# Naninator_and_Badger.net
KiCad netlist of a schematic drawn in EAGLE
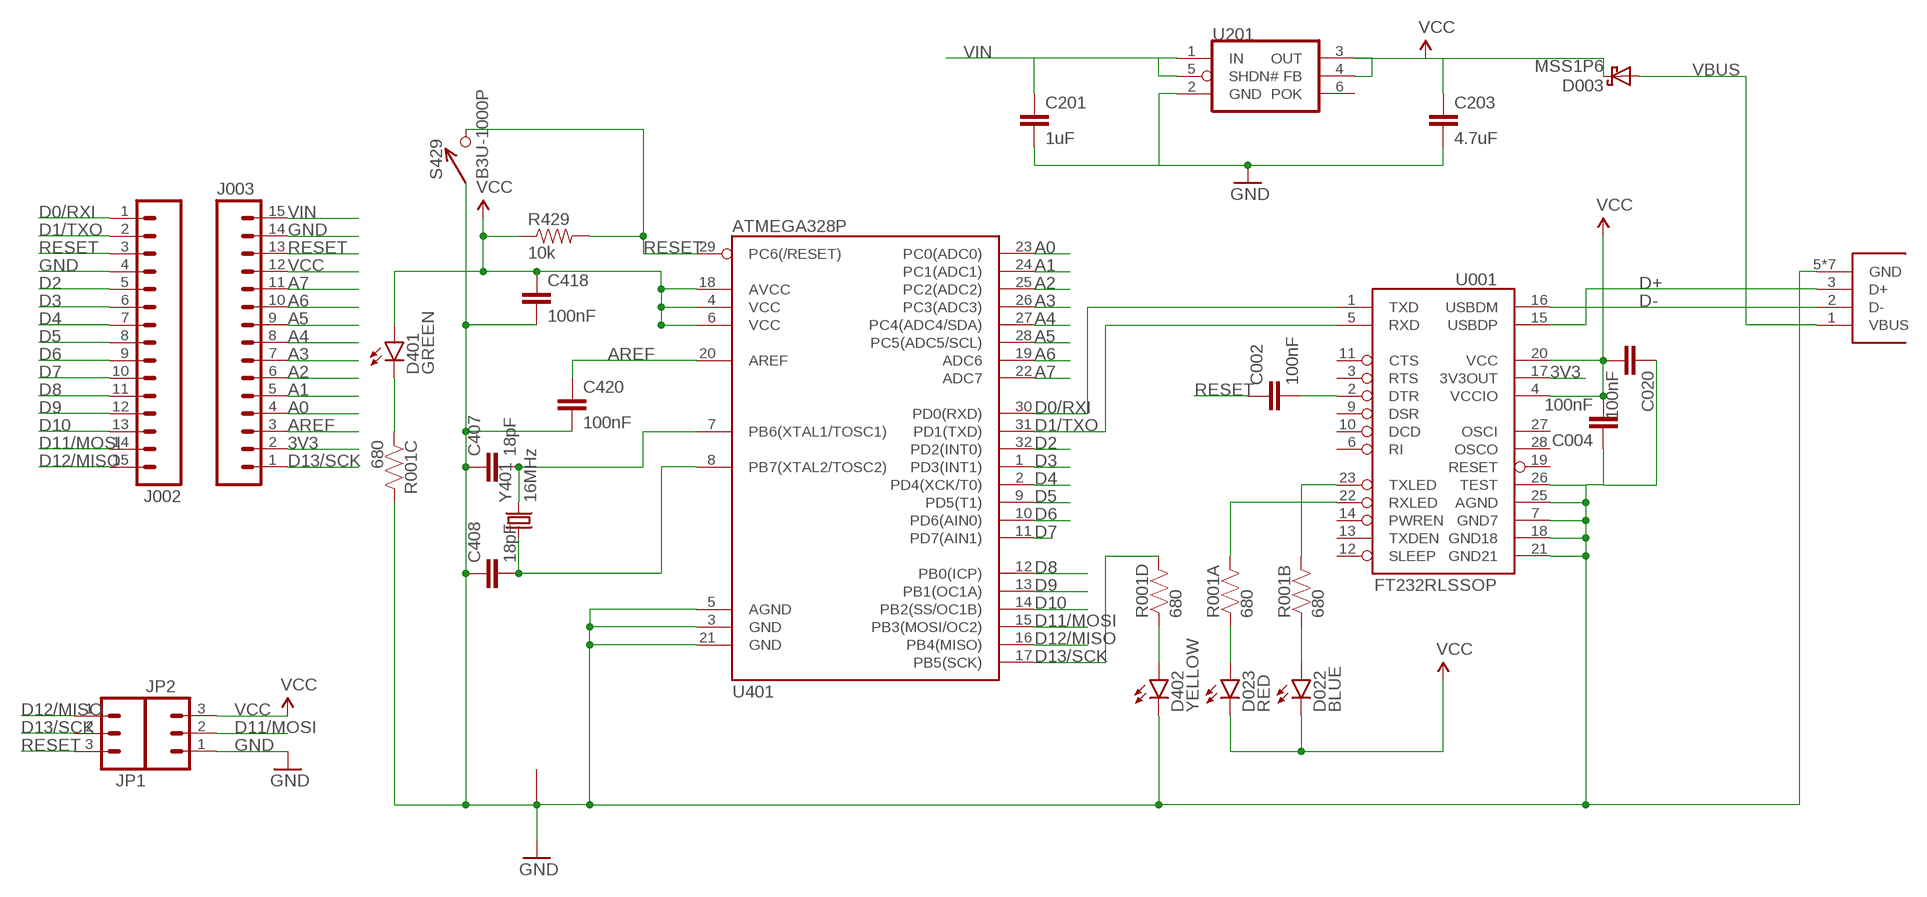
[diagram p0: schematic, sheet 1]

(export (version "E")
  (design (tool "Eeschema 10.0.6"))
  (components
    (comp (ref "C002")
      (value "100nF")
      (footprint "eagle-import:0402-CAP")
      (libsource (lib "eagle-import") (part "CAP0402-CAP"))
    )
    (comp (ref "C004")
      (value "100nF")
      (footprint "eagle-import:0402-CAP")
      (libsource (lib "eagle-import") (part "CAP0402-CAP"))
    )
    (comp (ref "C020")
      (value "100nF")
      (footprint "eagle-import:0402-CAP")
      (libsource (lib "eagle-import") (part "CAP0402-CAP"))
    )
    (comp (ref "C201")
      (value "1uF")
      (footprint "eagle-import:0402-CAP")
      (libsource (lib "eagle-import") (part "CAP0402-CAP"))
    )
    (comp (ref "C203")
      (value "4.7uF")
      (footprint "eagle-import:0402-CAP")
      (libsource (lib "eagle-import") (part "CAP0402-CAP"))
    )
    (comp (ref "C407")
      (value "18pF")
      (footprint "eagle-import:0402-CAP")
      (libsource (lib "eagle-import") (part "CAP0402-CAP"))
    )
    (comp (ref "C408")
      (value "18pF")
      (footprint "eagle-import:0402-CAP")
      (libsource (lib "eagle-import") (part "CAP0402-CAP"))
    )
    (comp (ref "C418")
      (value "100nF")
      (footprint "eagle-import:0402-CAP")
      (libsource (lib "eagle-import") (part "CAP0402-CAP"))
    )
    (comp (ref "C420")
      (value "100nF")
      (footprint "eagle-import:0402-CAP")
      (libsource (lib "eagle-import") (part "CAP0402-CAP"))
    )
    (comp (ref "D003")
      (value "MSS1P6")
      (footprint "eagle-import:MICROSMP")
      (libsource (lib "eagle-import") (part "MSS1P6"))
    )
    (comp (ref "D022")
      (value "BLUE")
      (footprint "eagle-import:LED-0603")
      (libsource (lib "eagle-import") (part "LED0603"))
    )
    (comp (ref "D023")
      (value "RED")
      (footprint "eagle-import:LED-0603")
      (libsource (lib "eagle-import") (part "LED0603"))
    )
    (comp (ref "D401")
      (value "GREEN")
      (footprint "eagle-import:LED-0603")
      (libsource (lib "eagle-import") (part "LED0603"))
    )
    (comp (ref "D402")
      (value "YELLOW")
      (footprint "eagle-import:LED-0603")
      (libsource (lib "eagle-import") (part "LED0603"))
    )
    (comp (ref "J001")
      (value "USB_MICROB_JSTFCI")
      (footprint "eagle-import:USB-MICROB-CONN-09505")
      (libsource (lib "eagle-import") (part "USB_MICROB_JSTFCI"))
    )
    (comp (ref "J002")
      (value "M15")
      (footprint "eagle-import:1X15")
      (libsource (lib "eagle-import") (part "M15"))
    )
    (comp (ref "J003")
      (value "M15")
      (footprint "eagle-import:1X15")
      (libsource (lib "eagle-import") (part "M15"))
    )
    (comp (ref "JP1")
      (value "M03PTH")
      (footprint "eagle-import:1X03")
      (libsource (lib "eagle-import") (part "M03PTH"))
    )
    (comp (ref "JP2")
      (value "M03PTH")
      (footprint "eagle-import:1X03")
      (libsource (lib "eagle-import") (part "M03PTH"))
    )
    (comp (ref "R001")
      (value "680")
      (footprint "eagle-import:CRA04")
      (fields (field (name "DIGIKEY") "CRA4S8680CT-ND"))
      (libsource (lib "eagle-import") (part "RP404"))
    )
    (comp (ref "R429")
      (value "10k")
      (footprint "eagle-import:0402-RES")
      (libsource (lib "eagle-import") (part "RESISTOR0402-RES"))
    )
    (comp (ref "S429")
      (value "B3U-1000P")
      (footprint "eagle-import:B3U-1000P")
      (libsource (lib "eagle-import") (part "B3U-1000P"))
    )
    (comp (ref "U001")
      (value "FT232RLSSOP")
      (footprint "eagle-import:SSOP28DB@1")
      (libsource (lib "eagle-import") (part "FT232RLSSOP"))
    )
    (comp (ref "U201")
      (value "MAX8881")
      (footprint "eagle-import:SOT-23-6")
      (libsource (lib "eagle-import") (part "MAX8881"))
    )
    (comp (ref "U401")
      (value "ATMEGA328P")
      (footprint "eagle-import:TQFP32-08@1")
      (libsource (lib "eagle-import") (part "ATMEGA168"))
    )
    (comp (ref "Y401")
      (value "16MHz")
      (footprint "eagle-import:CRYSTAL_SMD_2MM_2_5MM")
      (fields (field (name "DIGIKEY") "478-6955-1-ND"))
      (libsource (lib "eagle-import") (part "CX2520"))
    )
  )
  (nets
    (net (code "1") (name "/3V3") (class "Default")
      (node (ref "J003") (pin "2") (pinfunction "2_2") (pintype "passive"))
      (node (ref "U001") (pin "17") (pinfunction "3V3OUT_17") (pintype "output"))
    )
    (net (code "2") (name "/A0") (class "Default")
      (node (ref "J003") (pin "4") (pinfunction "4_4") (pintype "passive"))
      (node (ref "U401") (pin "23") (pinfunction "PC0(ADC0)_23") (pintype "bidirectional"))
    )
    (net (code "3") (name "/A1") (class "Default")
      (node (ref "J003") (pin "5") (pinfunction "5_5") (pintype "passive"))
      (node (ref "U401") (pin "24") (pinfunction "PC1(ADC1)_24") (pintype "bidirectional"))
    )
    (net (code "4") (name "/A2") (class "Default")
      (node (ref "J003") (pin "6") (pinfunction "6_6") (pintype "passive"))
      (node (ref "U401") (pin "25") (pinfunction "PC2(ADC2)_25") (pintype "bidirectional"))
    )
    (net (code "5") (name "/A3") (class "Default")
      (node (ref "J003") (pin "7") (pinfunction "7_7") (pintype "passive"))
      (node (ref "U401") (pin "26") (pinfunction "PC3(ADC3)_26") (pintype "bidirectional"))
    )
    (net (code "6") (name "/A4") (class "Default")
      (node (ref "J003") (pin "8") (pinfunction "8_8") (pintype "passive"))
      (node (ref "U401") (pin "27") (pinfunction "PC4(ADC4/SDA)_27") (pintype "bidirectional"))
    )
    (net (code "7") (name "/A5") (class "Default")
      (node (ref "J003") (pin "9") (pinfunction "9_9") (pintype "passive"))
      (node (ref "U401") (pin "28") (pinfunction "PC5(ADC5/SCL)_28") (pintype "bidirectional"))
    )
    (net (code "8") (name "/A6") (class "Default")
      (node (ref "J003") (pin "10") (pinfunction "10_10") (pintype "passive"))
      (node (ref "U401") (pin "19") (pinfunction "ADC6_19") (pintype "bidirectional"))
    )
    (net (code "9") (name "/A7") (class "Default")
      (node (ref "J003") (pin "11") (pinfunction "11_11") (pintype "passive"))
      (node (ref "U401") (pin "22") (pinfunction "ADC7_22") (pintype "bidirectional"))
    )
    (net (code "10") (name "/AREF") (class "Default")
      (node (ref "C420") (pin "1") (pinfunction "1_1") (pintype "passive"))
      (node (ref "J003") (pin "3") (pinfunction "3_3") (pintype "passive"))
      (node (ref "U401") (pin "20") (pinfunction "AREF_20") (pintype "bidirectional"))
    )
    (net (code "11") (name "/D+") (class "Default")
      (node (ref "J001") (pin "3") (pinfunction "D+_3") (pintype "bidirectional"))
      (node (ref "U001") (pin "15") (pinfunction "USBDP_15") (pintype "bidirectional"))
    )
    (net (code "12") (name "/D-") (class "Default")
      (node (ref "J001") (pin "2") (pinfunction "D-_2") (pintype "bidirectional"))
      (node (ref "U001") (pin "16") (pinfunction "USBDM_16") (pintype "bidirectional"))
    )
    (net (code "13") (name "/D0{slash}RXI") (class "Default")
      (node (ref "J002") (pin "1") (pinfunction "1_1") (pintype "passive"))
      (node (ref "U001") (pin "1") (pinfunction "TXD_1") (pintype "output"))
      (node (ref "U401") (pin "30") (pinfunction "PD0(RXD)_30") (pintype "bidirectional"))
    )
    (net (code "14") (name "/D1{slash}TXO") (class "Default")
      (node (ref "J002") (pin "2") (pinfunction "2_2") (pintype "passive"))
      (node (ref "U001") (pin "5") (pinfunction "RXD_5") (pintype "input"))
      (node (ref "U401") (pin "31") (pinfunction "PD1(TXD)_31") (pintype "bidirectional"))
    )
    (net (code "15") (name "/D2") (class "Default")
      (node (ref "J002") (pin "5") (pinfunction "5_5") (pintype "passive"))
      (node (ref "U401") (pin "32") (pinfunction "PD2(INT0)_32") (pintype "bidirectional"))
    )
    (net (code "16") (name "/D3") (class "Default")
      (node (ref "J002") (pin "6") (pinfunction "6_6") (pintype "passive"))
      (node (ref "U401") (pin "1") (pinfunction "PD3(INT1)_1") (pintype "bidirectional"))
    )
    (net (code "17") (name "/D4") (class "Default")
      (node (ref "J002") (pin "7") (pinfunction "7_7") (pintype "passive"))
      (node (ref "U401") (pin "2") (pinfunction "PD4(XCK/T0)_2") (pintype "bidirectional"))
    )
    (net (code "18") (name "/D5") (class "Default")
      (node (ref "J002") (pin "8") (pinfunction "8_8") (pintype "passive"))
      (node (ref "U401") (pin "9") (pinfunction "PD5(T1)_9") (pintype "bidirectional"))
    )
    (net (code "19") (name "/D6") (class "Default")
      (node (ref "J002") (pin "9") (pinfunction "9_9") (pintype "passive"))
      (node (ref "U401") (pin "10") (pinfunction "PD6(AIN0)_10") (pintype "bidirectional"))
    )
    (net (code "20") (name "/D7") (class "Default")
      (node (ref "J002") (pin "10") (pinfunction "10_10") (pintype "passive"))
      (node (ref "U401") (pin "11") (pinfunction "PD7(AIN1)_11") (pintype "bidirectional"))
    )
    (net (code "21") (name "/D8") (class "Default")
      (node (ref "J002") (pin "11") (pinfunction "11_11") (pintype "passive"))
      (node (ref "U401") (pin "12") (pinfunction "PB0(ICP)_12") (pintype "bidirectional"))
    )
    (net (code "22") (name "/D9") (class "Default")
      (node (ref "J002") (pin "12") (pinfunction "12_12") (pintype "passive"))
      (node (ref "U401") (pin "13") (pinfunction "PB1(OC1A)_13") (pintype "bidirectional"))
    )
    (net (code "23") (name "/D10") (class "Default")
      (node (ref "J002") (pin "13") (pinfunction "13_13") (pintype "passive"))
      (node (ref "U401") (pin "14") (pinfunction "PB2(SS/OC1B)_14") (pintype "bidirectional"))
    )
    (net (code "24") (name "/D11{slash}MOSI") (class "Default")
      (node (ref "J002") (pin "14") (pinfunction "14_14") (pintype "passive"))
      (node (ref "JP2") (pin "2") (pinfunction "2_2") (pintype "passive"))
      (node (ref "U401") (pin "15") (pinfunction "PB3(MOSI/OC2)_15") (pintype "bidirectional"))
    )
    (net (code "25") (name "/D12{slash}MISO") (class "Default")
      (node (ref "J002") (pin "15") (pinfunction "15_15") (pintype "passive"))
      (node (ref "JP1") (pin "1") (pinfunction "1_1") (pintype "passive"))
      (node (ref "U401") (pin "16") (pinfunction "PB4(MISO)_16") (pintype "bidirectional"))
    )
    (net (code "26") (name "/D13{slash}SCK") (class "Default")
      (node (ref "J003") (pin "1") (pinfunction "1_1") (pintype "passive"))
      (node (ref "JP1") (pin "2") (pinfunction "2_2") (pintype "passive"))
      (node (ref "R001") (pin "5") (pinfunction "2_5") (pintype "passive"))
      (node (ref "U401") (pin "17") (pinfunction "PB5(SCK)_17") (pintype "bidirectional"))
    )
    (net (code "27") (name "/RESET") (class "Default")
      (node (ref "C002") (pin "1") (pinfunction "1_1") (pintype "passive"))
      (node (ref "J002") (pin "3") (pinfunction "3_3") (pintype "passive"))
      (node (ref "J003") (pin "13") (pinfunction "13_13") (pintype "passive"))
      (node (ref "JP1") (pin "3") (pinfunction "3_3") (pintype "passive"))
      (node (ref "R429") (pin "2") (pinfunction "2_2") (pintype "passive"))
      (node (ref "S429") (pin "P$2") (pinfunction "2_P$2") (pintype "bidirectional"))
      (node (ref "U401") (pin "29") (pinfunction "PC6(/RESET)_29") (pintype "bidirectional"))
    )
    (net (code "28") (name "/VBUS") (class "Default")
      (node (ref "D003") (pin "A") (pinfunction "A_A") (pintype "passive"))
      (node (ref "J001") (pin "1") (pinfunction "VBUS_1") (pintype "bidirectional"))
    )
    (net (code "29") (name "/VIN") (class "Default")
      (node (ref "C201") (pin "1") (pinfunction "1_1") (pintype "passive"))
      (node (ref "J003") (pin "15") (pinfunction "15_15") (pintype "passive"))
      (node (ref "U201") (pin "1") (pinfunction "IN_1") (pintype "bidirectional"))
      (node (ref "U201") (pin "5") (pinfunction "SHDN#_5") (pintype "bidirectional"))
    )
    (net (code "30") (name "GND") (class "Default")
      (node (ref "C004") (pin "1") (pinfunction "1_1") (pintype "passive"))
      (node (ref "C020") (pin "1") (pinfunction "1_1") (pintype "passive"))
      (node (ref "C201") (pin "2") (pinfunction "2_2") (pintype "passive"))
      (node (ref "C203") (pin "2") (pinfunction "2_2") (pintype "passive"))
      (node (ref "C407") (pin "1") (pinfunction "1_1") (pintype "passive"))
      (node (ref "C408") (pin "1") (pinfunction "1_1") (pintype "passive"))
      (node (ref "C418") (pin "2") (pinfunction "2_2") (pintype "passive"))
      (node (ref "C420") (pin "2") (pinfunction "2_2") (pintype "passive"))
      (node (ref "D402") (pin "C") (pinfunction "C_C") (pintype "passive"))
      (node (ref "J001") (pin "5") (pinfunction "GND_5") (pintype "bidirectional"))
      (node (ref "J001") (pin "P1") (pinfunction "GND_P1") (pintype "bidirectional"))
      (node (ref "J001") (pin "P2") (pinfunction "GND_P2") (pintype "bidirectional"))
      (node (ref "J001") (pin "P3") (pinfunction "GND_P3") (pintype "bidirectional"))
      (node (ref "J001") (pin "P4") (pinfunction "GND_P4") (pintype "bidirectional"))
      (node (ref "J001") (pin "P5") (pinfunction "GND_P5") (pintype "bidirectional"))
      (node (ref "J001") (pin "P6") (pinfunction "GND_P6") (pintype "bidirectional"))
      (node (ref "J002") (pin "4") (pinfunction "4_4") (pintype "passive"))
      (node (ref "J003") (pin "14") (pinfunction "14_14") (pintype "passive"))
      (node (ref "JP2") (pin "1") (pinfunction "1_1") (pintype "passive"))
      (node (ref "R001") (pin "6") (pinfunction "2_6") (pintype "passive"))
      (node (ref "S429") (pin "P$1") (pinfunction "1_P$1") (pintype "bidirectional"))
      (node (ref "U001") (pin "18") (pinfunction "GND18_18") (pintype "power_in"))
      (node (ref "U001") (pin "21") (pinfunction "GND21_21") (pintype "power_in"))
      (node (ref "U001") (pin "25") (pinfunction "AGND_25") (pintype "power_in"))
      (node (ref "U001") (pin "26") (pinfunction "TEST_26") (pintype "input"))
      (node (ref "U001") (pin "7") (pinfunction "GND7_7") (pintype "power_in"))
      (node (ref "U201") (pin "2") (pinfunction "GND_2") (pintype "bidirectional"))
      (node (ref "U401") (pin "21") (pinfunction "GND_21") (pintype "bidirectional"))
      (node (ref "U401") (pin "3") (pinfunction "GND_3") (pintype "bidirectional"))
      (node (ref "U401") (pin "5") (pinfunction "AGND_5") (pintype "bidirectional"))
      (node (ref "Y401") (pin "2") (pinfunction "1_2") (pintype "bidirectional"))
      (node (ref "Y401") (pin "4") (pinfunction "1_4") (pintype "bidirectional"))
    )
    (net (code "31") (name "Net-(D023-PadA)") (class "Default")
      (node (ref "D023") (pin "A") (pinfunction "A_A") (pintype "passive"))
      (node (ref "R001") (pin "1") (pinfunction "1_1") (pintype "passive"))
    )
    (net (code "32") (name "Net-(R001A-2)") (class "Default")
      (node (ref "R001") (pin "8") (pinfunction "2_8") (pintype "passive"))
      (node (ref "U001") (pin "22") (pinfunction "RXLED_22") (pintype "input"))
    )
    (net (code "33") (name "Net-(R001B-1)") (class "Default")
      (node (ref "D022") (pin "A") (pinfunction "A_A") (pintype "passive"))
      (node (ref "R001") (pin "2") (pinfunction "1_2") (pintype "passive"))
    )
    (net (code "34") (name "Net-(R001B-2)") (class "Default")
      (node (ref "R001") (pin "7") (pinfunction "2_7") (pintype "passive"))
      (node (ref "U001") (pin "23") (pinfunction "TXLED_23") (pintype "input"))
    )
    (net (code "35") (name "Net-(R001C-1)") (class "Default")
      (node (ref "D401") (pin "C") (pinfunction "C_C") (pintype "passive"))
      (node (ref "R001") (pin "3") (pinfunction "1_3") (pintype "passive"))
    )
    (net (code "36") (name "Net-(R001D-1)") (class "Default")
      (node (ref "D402") (pin "A") (pinfunction "A_A") (pintype "passive"))
      (node (ref "R001") (pin "4") (pinfunction "1_4") (pintype "passive"))
    )
    (net (code "37") (name "Net-(U001-DTR)") (class "Default")
      (node (ref "C002") (pin "2") (pinfunction "2_2") (pintype "passive"))
      (node (ref "U001") (pin "2") (pinfunction "DTR_2") (pintype "output"))
    )
    (net (code "38") (name "Net-(U401-PB6(XTAL1{slash}TOSC1))") (class "Default")
      (node (ref "C407") (pin "2") (pinfunction "2_2") (pintype "passive"))
      (node (ref "U401") (pin "7") (pinfunction "PB6(XTAL1/TOSC1)_7") (pintype "bidirectional"))
      (node (ref "Y401") (pin "3") (pinfunction "2_3") (pintype "passive"))
    )
    (net (code "39") (name "Net-(U401-PB7(XTAL2{slash}TOSC2))") (class "Default")
      (node (ref "C408") (pin "2") (pinfunction "2_2") (pintype "passive"))
      (node (ref "U401") (pin "8") (pinfunction "PB7(XTAL2/TOSC2)_8") (pintype "bidirectional"))
      (node (ref "Y401") (pin "1") (pinfunction "1_1") (pintype "passive"))
    )
    (net (code "40") (name "VCC") (class "Default")
      (node (ref "C004") (pin "2") (pinfunction "2_2") (pintype "passive"))
      (node (ref "C020") (pin "2") (pinfunction "2_2") (pintype "passive"))
      (node (ref "C203") (pin "1") (pinfunction "1_1") (pintype "passive"))
      (node (ref "C418") (pin "1") (pinfunction "1_1") (pintype "passive"))
      (node (ref "D003") (pin "K") (pinfunction "K_K") (pintype "passive"))
      (node (ref "D022") (pin "C") (pinfunction "C_C") (pintype "passive"))
      (node (ref "D023") (pin "C") (pinfunction "C_C") (pintype "passive"))
      (node (ref "D401") (pin "A") (pinfunction "A_A") (pintype "passive"))
      (node (ref "J003") (pin "12") (pinfunction "12_12") (pintype "passive"))
      (node (ref "JP2") (pin "3") (pinfunction "3_3") (pintype "passive"))
      (node (ref "R429") (pin "1") (pinfunction "1_1") (pintype "passive"))
      (node (ref "U001") (pin "20") (pinfunction "VCC_20") (pintype "power_in"))
      (node (ref "U001") (pin "4") (pinfunction "VCCIO_4") (pintype "power_in"))
      (node (ref "U201") (pin "3") (pinfunction "OUT_3") (pintype "bidirectional"))
      (node (ref "U201") (pin "4") (pinfunction "FB_4") (pintype "bidirectional"))
      (node (ref "U401") (pin "18") (pinfunction "AVCC_18") (pintype "bidirectional"))
      (node (ref "U401") (pin "4") (pinfunction "VCC_4") (pintype "bidirectional"))
      (node (ref "U401") (pin "6") (pinfunction "VCC_6") (pintype "bidirectional"))
    )
    (net (code "41") (name "unconnected-(U001-CTS-Pad11)") (class "Default")
      (node (ref "U001") (pin "11") (pinfunction "CTS_11") (pintype "input"))
    )
    (net (code "42") (name "unconnected-(U001-DCD-Pad10)") (class "Default")
      (node (ref "U001") (pin "10") (pinfunction "DCD_10") (pintype "input"))
    )
    (net (code "43") (name "unconnected-(U001-DSR-Pad9)") (class "Default")
      (node (ref "U001") (pin "9") (pinfunction "DSR_9") (pintype "input"))
    )
    (net (code "44") (name "unconnected-(U001-OSCI-Pad27)") (class "Default")
      (node (ref "U001") (pin "27") (pinfunction "OSCI_27") (pintype "input"))
    )
    (net (code "45") (name "unconnected-(U001-OSCO-Pad28)") (class "Default")
      (node (ref "U001") (pin "28") (pinfunction "OSCO_28") (pintype "output"))
    )
    (net (code "46") (name "unconnected-(U001-PWREN-Pad14)") (class "Default")
      (node (ref "U001") (pin "14") (pinfunction "PWREN_14") (pintype "input"))
    )
    (net (code "47") (name "unconnected-(U001-RESET-Pad19)") (class "Default")
      (node (ref "U001") (pin "19") (pinfunction "RESET_19") (pintype "input"))
    )
    (net (code "48") (name "unconnected-(U001-RI-Pad6)") (class "Default")
      (node (ref "U001") (pin "6") (pinfunction "RI_6") (pintype "input"))
    )
    (net (code "49") (name "unconnected-(U001-RTS-Pad3)") (class "Default")
      (node (ref "U001") (pin "3") (pinfunction "RTS_3") (pintype "output"))
    )
    (net (code "50") (name "unconnected-(U001-SLEEP-Pad12)") (class "Default")
      (node (ref "U001") (pin "12") (pinfunction "SLEEP_12") (pintype "input"))
    )
    (net (code "51") (name "unconnected-(U001-TXDEN-Pad13)") (class "Default")
      (node (ref "U001") (pin "13") (pinfunction "TXDEN_13") (pintype "input"))
    )
    (net (code "52") (name "unconnected-(U201-POK-Pad6)") (class "Default")
      (node (ref "U201") (pin "6") (pinfunction "POK_6") (pintype "bidirectional"))
    )
  )
)
